# axiom_beta_plugin_module_3xmDP_v1_1.net
KiCad netlist of a schematic drawn in EAGLE
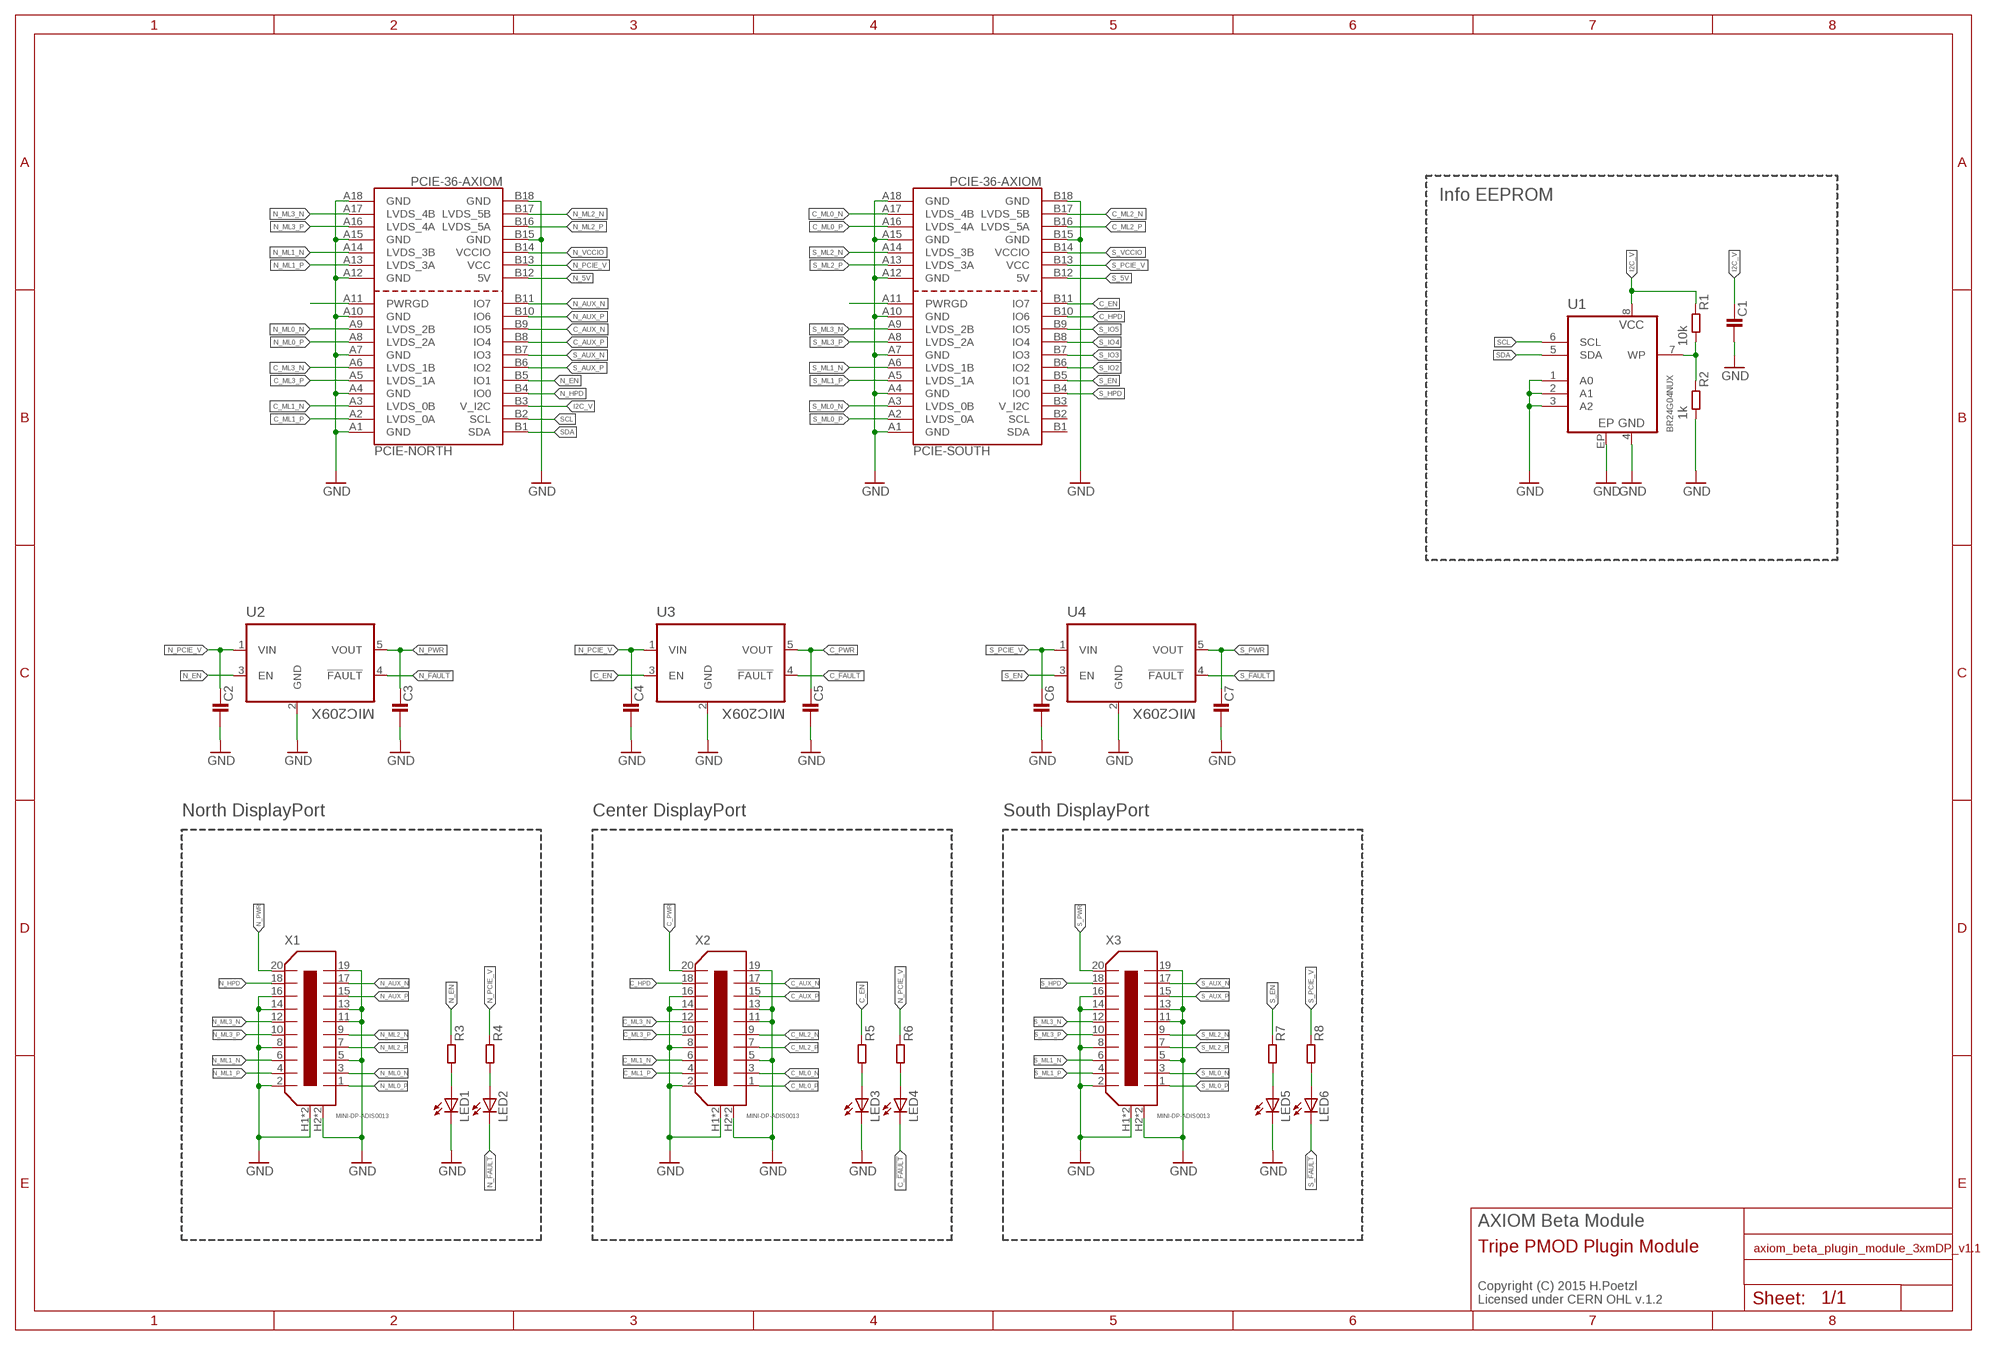
[diagram p0: schematic, sheet 1]

(export (version "E")
  (design (tool "Eeschema 10.0.6"))
  (components
    (comp (ref "C1")
      (value "C0402-B")
      (footprint "eagle-import:0402-B")
      (libsource (lib "eagle-import") (part "C0402-B"))
    )
    (comp (ref "C2")
      (value "C0603-B")
      (footprint "eagle-import:0603-B")
      (libsource (lib "eagle-import") (part "C0603-B"))
    )
    (comp (ref "C3")
      (value "C0603-B")
      (footprint "eagle-import:0603-B")
      (libsource (lib "eagle-import") (part "C0603-B"))
    )
    (comp (ref "C4")
      (value "C0603-B")
      (footprint "eagle-import:0603-B")
      (libsource (lib "eagle-import") (part "C0603-B"))
    )
    (comp (ref "C5")
      (value "C0603-B")
      (footprint "eagle-import:0603-B")
      (libsource (lib "eagle-import") (part "C0603-B"))
    )
    (comp (ref "C6")
      (value "C0603-B")
      (footprint "eagle-import:0603-B")
      (libsource (lib "eagle-import") (part "C0603-B"))
    )
    (comp (ref "C7")
      (value "C0603-B")
      (footprint "eagle-import:0603-B")
      (libsource (lib "eagle-import") (part "C0603-B"))
    )
    (comp (ref "LED1")
      (value "LEDCHIPLED_0603")
      (footprint "eagle-import:CHIPLED_0603")
      (libsource (lib "eagle-import") (part "LEDCHIPLED_0603"))
    )
    (comp (ref "LED2")
      (value "LEDCHIPLED_0603")
      (footprint "eagle-import:CHIPLED_0603")
      (libsource (lib "eagle-import") (part "LEDCHIPLED_0603"))
    )
    (comp (ref "LED3")
      (value "LEDCHIPLED_0603")
      (footprint "eagle-import:CHIPLED_0603")
      (libsource (lib "eagle-import") (part "LEDCHIPLED_0603"))
    )
    (comp (ref "LED4")
      (value "LEDCHIPLED_0603")
      (footprint "eagle-import:CHIPLED_0603")
      (libsource (lib "eagle-import") (part "LEDCHIPLED_0603"))
    )
    (comp (ref "LED5")
      (value "LEDCHIPLED_0603")
      (footprint "eagle-import:CHIPLED_0603")
      (libsource (lib "eagle-import") (part "LEDCHIPLED_0603"))
    )
    (comp (ref "LED6")
      (value "LEDCHIPLED_0603")
      (footprint "eagle-import:CHIPLED_0603")
      (libsource (lib "eagle-import") (part "LEDCHIPLED_0603"))
    )
    (comp (ref "PCIE-NORTH")
      (value "PCIE-36-AXIOM")
      (footprint "eagle-import:PCIE-36-AXIOM")
      (libsource (lib "eagle-import") (part "PCIE-36-AXIOM"))
    )
    (comp (ref "PCIE-SOUTH")
      (value "PCIE-36-AXIOM")
      (footprint "eagle-import:PCIE-36-AXIOM")
      (libsource (lib "eagle-import") (part "PCIE-36-AXIOM"))
    )
    (comp (ref "R1")
      (value "10k")
      (footprint "eagle-import:0402-B")
      (libsource (lib "eagle-import") (part "R0402-B"))
    )
    (comp (ref "R2")
      (value "1k")
      (footprint "eagle-import:0402-B")
      (libsource (lib "eagle-import") (part "R0402-B"))
    )
    (comp (ref "R3")
      (value "R0402-B")
      (footprint "eagle-import:0402-B")
      (libsource (lib "eagle-import") (part "R0402-B"))
    )
    (comp (ref "R4")
      (value "R0402-B")
      (footprint "eagle-import:0402-B")
      (libsource (lib "eagle-import") (part "R0402-B"))
    )
    (comp (ref "R5")
      (value "R0402-B")
      (footprint "eagle-import:0402-B")
      (libsource (lib "eagle-import") (part "R0402-B"))
    )
    (comp (ref "R6")
      (value "R0402-B")
      (footprint "eagle-import:0402-B")
      (libsource (lib "eagle-import") (part "R0402-B"))
    )
    (comp (ref "R7")
      (value "R0402-B")
      (footprint "eagle-import:0402-B")
      (libsource (lib "eagle-import") (part "R0402-B"))
    )
    (comp (ref "R8")
      (value "R0402-B")
      (footprint "eagle-import:0402-B")
      (libsource (lib "eagle-import") (part "R0402-B"))
    )
    (comp (ref "U1")
      (value "BR24G04NUX")
      (footprint "eagle-import:DFN200X300X100-9N")
      (libsource (lib "eagle-import") (part "BR24G04NUX"))
    )
    (comp (ref "U2")
      (value "MIC209X")
      (footprint "eagle-import:SOT95P280X145-5N")
      (fields (field (name "MPN") "MIC2090-1YM5TR"))
      (libsource (lib "eagle-import") (part "MIC209X"))
    )
    (comp (ref "U3")
      (value "MIC209X")
      (footprint "eagle-import:SOT95P280X145-5N")
      (fields (field (name "MPN") "MIC2090-1YM5TR"))
      (libsource (lib "eagle-import") (part "MIC209X"))
    )
    (comp (ref "U4")
      (value "MIC209X")
      (footprint "eagle-import:SOT95P280X145-5N")
      (fields (field (name "MPN") "MIC2090-1YM5TR"))
      (libsource (lib "eagle-import") (part "MIC209X"))
    )
    (comp (ref "X1")
      (value "MINI-DP-ADIS0013")
      (footprint "eagle-import:ADIS0013")
      (libsource (lib "eagle-import") (part "MINI-DP-ADIS0013"))
    )
    (comp (ref "X2")
      (value "MINI-DP-ADIS0013")
      (footprint "eagle-import:ADIS0013")
      (libsource (lib "eagle-import") (part "MINI-DP-ADIS0013"))
    )
    (comp (ref "X3")
      (value "MINI-DP-ADIS0013")
      (footprint "eagle-import:ADIS0013")
      (libsource (lib "eagle-import") (part "MINI-DP-ADIS0013"))
    )
  )
  (nets
    (net (code "1") (name "/C_~{FAULT}") (class "Default")
      (node (ref "LED4") (pin "C") (pinfunction "C_C") (pintype "passive"))
      (node (ref "U3") (pin "4") (pinfunction "~{FAULT}_4") (pintype "output"))
    )
    (net (code "2") (name "/N_~{FAULT}") (class "Default")
      (node (ref "LED2") (pin "C") (pinfunction "C_C") (pintype "passive"))
      (node (ref "U2") (pin "4") (pinfunction "~{FAULT}_4") (pintype "output"))
    )
    (net (code "3") (name "/S_~{FAULT}") (class "Default")
      (node (ref "LED6") (pin "C") (pinfunction "C_C") (pintype "passive"))
      (node (ref "U4") (pin "4") (pinfunction "~{FAULT}_4") (pintype "output"))
    )
    (net (code "4") (name "C_AUX_N") (class "Default")
      (node (ref "PCIE-NORTH") (pin "B9") (pinfunction "IO5_B9") (pintype "passive"))
      (node (ref "X2") (pin "17") (pinfunction "17_17") (pintype "passive"))
    )
    (net (code "5") (name "C_AUX_P") (class "Default")
      (node (ref "PCIE-NORTH") (pin "B8") (pinfunction "IO4_B8") (pintype "passive"))
      (node (ref "X2") (pin "15") (pinfunction "15_15") (pintype "passive"))
    )
    (net (code "6") (name "C_EN") (class "Default")
      (node (ref "PCIE-SOUTH") (pin "B11") (pinfunction "IO7_B11") (pintype "passive"))
      (node (ref "R5") (pin "1") (pinfunction "1_1") (pintype "passive"))
      (node (ref "U3") (pin "3") (pinfunction "EN_3") (pintype "input"))
    )
    (net (code "7") (name "C_HPD") (class "Default")
      (node (ref "PCIE-SOUTH") (pin "B10") (pinfunction "IO6_B10") (pintype "passive"))
      (node (ref "X2") (pin "18") (pinfunction "18_18") (pintype "passive"))
    )
    (net (code "8") (name "C_ML0_N") (class "Default")
      (node (ref "PCIE-SOUTH") (pin "A17") (pinfunction "LVDS_4B_A17") (pintype "passive"))
      (node (ref "X2") (pin "3") (pinfunction "3_3") (pintype "passive"))
    )
    (net (code "9") (name "C_ML0_P") (class "Default")
      (node (ref "PCIE-SOUTH") (pin "A16") (pinfunction "LVDS_4A_A16") (pintype "passive"))
      (node (ref "X2") (pin "1") (pinfunction "1_1") (pintype "passive"))
    )
    (net (code "10") (name "C_ML1_N") (class "Default")
      (node (ref "PCIE-NORTH") (pin "A3") (pinfunction "LVDS_0B_A3") (pintype "passive"))
      (node (ref "X2") (pin "6") (pinfunction "6_6") (pintype "passive"))
    )
    (net (code "11") (name "C_ML1_P") (class "Default")
      (node (ref "PCIE-NORTH") (pin "A2") (pinfunction "LVDS_0A_A2") (pintype "passive"))
      (node (ref "X2") (pin "4") (pinfunction "4_4") (pintype "passive"))
    )
    (net (code "12") (name "C_ML2_N") (class "Default")
      (node (ref "PCIE-SOUTH") (pin "B17") (pinfunction "LVDS_5B_B17") (pintype "passive"))
      (node (ref "X2") (pin "9") (pinfunction "9_9") (pintype "passive"))
    )
    (net (code "13") (name "C_ML2_P") (class "Default")
      (node (ref "PCIE-SOUTH") (pin "B16") (pinfunction "LVDS_5A_B16") (pintype "passive"))
      (node (ref "X2") (pin "7") (pinfunction "7_7") (pintype "passive"))
    )
    (net (code "14") (name "C_ML3_N") (class "Default")
      (node (ref "PCIE-NORTH") (pin "A6") (pinfunction "LVDS_1B_A6") (pintype "passive"))
      (node (ref "X2") (pin "12") (pinfunction "12_12") (pintype "passive"))
    )
    (net (code "15") (name "C_ML3_P") (class "Default")
      (node (ref "PCIE-NORTH") (pin "A5") (pinfunction "LVDS_1A_A5") (pintype "passive"))
      (node (ref "X2") (pin "10") (pinfunction "10_10") (pintype "passive"))
    )
    (net (code "16") (name "C_PWR") (class "Default")
      (node (ref "C5") (pin "1") (pinfunction "1_1") (pintype "passive"))
      (node (ref "U3") (pin "5") (pinfunction "VOUT_5") (pintype "output"))
      (node (ref "X2") (pin "20") (pinfunction "20_20") (pintype "passive"))
    )
    (net (code "17") (name "GND") (class "Default")
      (node (ref "C1") (pin "2") (pinfunction "2_2") (pintype "passive"))
      (node (ref "C2") (pin "2") (pinfunction "2_2") (pintype "passive"))
      (node (ref "C3") (pin "2") (pinfunction "2_2") (pintype "passive"))
      (node (ref "C4") (pin "2") (pinfunction "2_2") (pintype "passive"))
      (node (ref "C5") (pin "2") (pinfunction "2_2") (pintype "passive"))
      (node (ref "C6") (pin "2") (pinfunction "2_2") (pintype "passive"))
      (node (ref "C7") (pin "2") (pinfunction "2_2") (pintype "passive"))
      (node (ref "LED1") (pin "C") (pinfunction "C_C") (pintype "passive"))
      (node (ref "LED3") (pin "C") (pinfunction "C_C") (pintype "passive"))
      (node (ref "LED5") (pin "C") (pinfunction "C_C") (pintype "passive"))
      (node (ref "PCIE-NORTH") (pin "A1") (pinfunction "GND_A1") (pintype "passive"))
      (node (ref "PCIE-NORTH") (pin "A10") (pinfunction "GND_A10") (pintype "passive"))
      (node (ref "PCIE-NORTH") (pin "A12") (pinfunction "GND_A12") (pintype "passive"))
      (node (ref "PCIE-NORTH") (pin "A15") (pinfunction "GND_A15") (pintype "passive"))
      (node (ref "PCIE-NORTH") (pin "A18") (pinfunction "GND_A18") (pintype "passive"))
      (node (ref "PCIE-NORTH") (pin "A4") (pinfunction "GND_A4") (pintype "passive"))
      (node (ref "PCIE-NORTH") (pin "A7") (pinfunction "GND_A7") (pintype "passive"))
      (node (ref "PCIE-NORTH") (pin "B15") (pinfunction "GND_B15") (pintype "passive"))
      (node (ref "PCIE-NORTH") (pin "B18") (pinfunction "GND_B18") (pintype "passive"))
      (node (ref "PCIE-SOUTH") (pin "A1") (pinfunction "GND_A1") (pintype "passive"))
      (node (ref "PCIE-SOUTH") (pin "A10") (pinfunction "GND_A10") (pintype "passive"))
      (node (ref "PCIE-SOUTH") (pin "A12") (pinfunction "GND_A12") (pintype "passive"))
      (node (ref "PCIE-SOUTH") (pin "A15") (pinfunction "GND_A15") (pintype "passive"))
      (node (ref "PCIE-SOUTH") (pin "A18") (pinfunction "GND_A18") (pintype "passive"))
      (node (ref "PCIE-SOUTH") (pin "A4") (pinfunction "GND_A4") (pintype "passive"))
      (node (ref "PCIE-SOUTH") (pin "A7") (pinfunction "GND_A7") (pintype "passive"))
      (node (ref "PCIE-SOUTH") (pin "B15") (pinfunction "GND_B15") (pintype "passive"))
      (node (ref "PCIE-SOUTH") (pin "B18") (pinfunction "GND_B18") (pintype "passive"))
      (node (ref "R2") (pin "2") (pinfunction "2_2") (pintype "passive"))
      (node (ref "U1") (pin "1") (pinfunction "A0_1") (pintype "input"))
      (node (ref "U1") (pin "2") (pinfunction "A1_2") (pintype "input"))
      (node (ref "U1") (pin "3") (pinfunction "A2_3") (pintype "input"))
      (node (ref "U1") (pin "4") (pinfunction "GND_4") (pintype "passive"))
      (node (ref "U1") (pin "EP") (pinfunction "EP_EP") (pintype "passive"))
      (node (ref "U2") (pin "2") (pinfunction "GND_2") (pintype "passive"))
      (node (ref "U3") (pin "2") (pinfunction "GND_2") (pintype "passive"))
      (node (ref "U4") (pin "2") (pinfunction "GND_2") (pintype "passive"))
      (node (ref "X1") (pin "11") (pinfunction "11_11") (pintype "passive"))
      (node (ref "X1") (pin "13") (pinfunction "13_13") (pintype "passive"))
      (node (ref "X1") (pin "14") (pinfunction "14_14") (pintype "passive"))
      (node (ref "X1") (pin "16") (pinfunction "16_16") (pintype "passive"))
      (node (ref "X1") (pin "19") (pinfunction "19_19") (pintype "passive"))
      (node (ref "X1") (pin "2") (pinfunction "2_2") (pintype "passive"))
      (node (ref "X1") (pin "5") (pinfunction "5_5") (pintype "passive"))
      (node (ref "X1") (pin "8") (pinfunction "8_8") (pintype "passive"))
      (node (ref "X1") (pin "H1") (pinfunction "M_H1") (pintype "input"))
      (node (ref "X1") (pin "H2") (pinfunction "M_H2") (pintype "input"))
      (node (ref "X1") (pin "H3") (pinfunction "M_H3") (pintype "input"))
      (node (ref "X1") (pin "H4") (pinfunction "M_H4") (pintype "input"))
      (node (ref "X2") (pin "11") (pinfunction "11_11") (pintype "passive"))
      (node (ref "X2") (pin "13") (pinfunction "13_13") (pintype "passive"))
      (node (ref "X2") (pin "14") (pinfunction "14_14") (pintype "passive"))
      (node (ref "X2") (pin "16") (pinfunction "16_16") (pintype "passive"))
      (node (ref "X2") (pin "19") (pinfunction "19_19") (pintype "passive"))
      (node (ref "X2") (pin "2") (pinfunction "2_2") (pintype "passive"))
      (node (ref "X2") (pin "5") (pinfunction "5_5") (pintype "passive"))
      (node (ref "X2") (pin "8") (pinfunction "8_8") (pintype "passive"))
      (node (ref "X2") (pin "H1") (pinfunction "M_H1") (pintype "input"))
      (node (ref "X2") (pin "H2") (pinfunction "M_H2") (pintype "input"))
      (node (ref "X2") (pin "H3") (pinfunction "M_H3") (pintype "input"))
      (node (ref "X2") (pin "H4") (pinfunction "M_H4") (pintype "input"))
      (node (ref "X3") (pin "11") (pinfunction "11_11") (pintype "passive"))
      (node (ref "X3") (pin "13") (pinfunction "13_13") (pintype "passive"))
      (node (ref "X3") (pin "14") (pinfunction "14_14") (pintype "passive"))
      (node (ref "X3") (pin "16") (pinfunction "16_16") (pintype "passive"))
      (node (ref "X3") (pin "19") (pinfunction "19_19") (pintype "passive"))
      (node (ref "X3") (pin "2") (pinfunction "2_2") (pintype "passive"))
      (node (ref "X3") (pin "5") (pinfunction "5_5") (pintype "passive"))
      (node (ref "X3") (pin "8") (pinfunction "8_8") (pintype "passive"))
      (node (ref "X3") (pin "H1") (pinfunction "M_H1") (pintype "input"))
      (node (ref "X3") (pin "H2") (pinfunction "M_H2") (pintype "input"))
      (node (ref "X3") (pin "H3") (pinfunction "M_H3") (pintype "input"))
      (node (ref "X3") (pin "H4") (pinfunction "M_H4") (pintype "input"))
    )
    (net (code "18") (name "I2C_V") (class "Default")
      (node (ref "C1") (pin "1") (pinfunction "1_1") (pintype "passive"))
      (node (ref "PCIE-NORTH") (pin "B3") (pinfunction "V_I2C_B3") (pintype "passive"))
      (node (ref "R1") (pin "1") (pinfunction "1_1") (pintype "passive"))
      (node (ref "U1") (pin "8") (pinfunction "VCC_8") (pintype "power_in"))
    )
    (net (code "19") (name "N_5V") (class "Default")
      (node (ref "PCIE-NORTH") (pin "B12") (pinfunction "5V_B12") (pintype "passive"))
    )
    (net (code "20") (name "N_AUX_N") (class "Default")
      (node (ref "PCIE-NORTH") (pin "B11") (pinfunction "IO7_B11") (pintype "passive"))
      (node (ref "X1") (pin "17") (pinfunction "17_17") (pintype "passive"))
    )
    (net (code "21") (name "N_AUX_P") (class "Default")
      (node (ref "PCIE-NORTH") (pin "B10") (pinfunction "IO6_B10") (pintype "passive"))
      (node (ref "X1") (pin "15") (pinfunction "15_15") (pintype "passive"))
    )
    (net (code "22") (name "N_EN") (class "Default")
      (node (ref "PCIE-NORTH") (pin "B5") (pinfunction "IO1_B5") (pintype "passive"))
      (node (ref "R3") (pin "1") (pinfunction "1_1") (pintype "passive"))
      (node (ref "U2") (pin "3") (pinfunction "EN_3") (pintype "input"))
    )
    (net (code "23") (name "N_HPD") (class "Default")
      (node (ref "PCIE-NORTH") (pin "B4") (pinfunction "IO0_B4") (pintype "passive"))
      (node (ref "X1") (pin "18") (pinfunction "18_18") (pintype "passive"))
    )
    (net (code "24") (name "N_ML0_N") (class "Default")
      (node (ref "PCIE-NORTH") (pin "A9") (pinfunction "LVDS_2B_A9") (pintype "passive"))
      (node (ref "X1") (pin "3") (pinfunction "3_3") (pintype "passive"))
    )
    (net (code "25") (name "N_ML0_P") (class "Default")
      (node (ref "PCIE-NORTH") (pin "A8") (pinfunction "LVDS_2A_A8") (pintype "passive"))
      (node (ref "X1") (pin "1") (pinfunction "1_1") (pintype "passive"))
    )
    (net (code "26") (name "N_ML1_N") (class "Default")
      (node (ref "PCIE-NORTH") (pin "A14") (pinfunction "LVDS_3B_A14") (pintype "passive"))
      (node (ref "X1") (pin "6") (pinfunction "6_6") (pintype "passive"))
    )
    (net (code "27") (name "N_ML1_P") (class "Default")
      (node (ref "PCIE-NORTH") (pin "A13") (pinfunction "LVDS_3A_A13") (pintype "passive"))
      (node (ref "X1") (pin "4") (pinfunction "4_4") (pintype "passive"))
    )
    (net (code "28") (name "N_ML2_N") (class "Default")
      (node (ref "PCIE-NORTH") (pin "B17") (pinfunction "LVDS_5B_B17") (pintype "passive"))
      (node (ref "X1") (pin "9") (pinfunction "9_9") (pintype "passive"))
    )
    (net (code "29") (name "N_ML2_P") (class "Default")
      (node (ref "PCIE-NORTH") (pin "B16") (pinfunction "LVDS_5A_B16") (pintype "passive"))
      (node (ref "X1") (pin "7") (pinfunction "7_7") (pintype "passive"))
    )
    (net (code "30") (name "N_ML3_N") (class "Default")
      (node (ref "PCIE-NORTH") (pin "A17") (pinfunction "LVDS_4B_A17") (pintype "passive"))
      (node (ref "X1") (pin "12") (pinfunction "12_12") (pintype "passive"))
    )
    (net (code "31") (name "N_ML3_P") (class "Default")
      (node (ref "PCIE-NORTH") (pin "A16") (pinfunction "LVDS_4A_A16") (pintype "passive"))
      (node (ref "X1") (pin "10") (pinfunction "10_10") (pintype "passive"))
    )
    (net (code "32") (name "N_PCIE_V") (class "Default")
      (node (ref "C2") (pin "1") (pinfunction "1_1") (pintype "passive"))
      (node (ref "C4") (pin "1") (pinfunction "1_1") (pintype "passive"))
      (node (ref "PCIE-NORTH") (pin "B13") (pinfunction "VCC_B13") (pintype "passive"))
      (node (ref "R4") (pin "1") (pinfunction "1_1") (pintype "passive"))
      (node (ref "R6") (pin "1") (pinfunction "1_1") (pintype "passive"))
      (node (ref "U2") (pin "1") (pinfunction "VIN_1") (pintype "input"))
      (node (ref "U3") (pin "1") (pinfunction "VIN_1") (pintype "input"))
    )
    (net (code "33") (name "N_PWR") (class "Default")
      (node (ref "C3") (pin "1") (pinfunction "1_1") (pintype "passive"))
      (node (ref "U2") (pin "5") (pinfunction "VOUT_5") (pintype "output"))
      (node (ref "X1") (pin "20") (pinfunction "20_20") (pintype "passive"))
    )
    (net (code "34") (name "N_VCCIO") (class "Default")
      (node (ref "PCIE-NORTH") (pin "B14") (pinfunction "VCCIO_B14") (pintype "passive"))
    )
    (net (code "35") (name "Net-(LED1-PadA)") (class "Default")
      (node (ref "LED1") (pin "A") (pinfunction "A_A") (pintype "passive"))
      (node (ref "R3") (pin "2") (pinfunction "2_2") (pintype "passive"))
    )
    (net (code "36") (name "Net-(LED2-PadA)") (class "Default")
      (node (ref "LED2") (pin "A") (pinfunction "A_A") (pintype "passive"))
      (node (ref "R4") (pin "2") (pinfunction "2_2") (pintype "passive"))
    )
    (net (code "37") (name "Net-(LED3-PadA)") (class "Default")
      (node (ref "LED3") (pin "A") (pinfunction "A_A") (pintype "passive"))
      (node (ref "R5") (pin "2") (pinfunction "2_2") (pintype "passive"))
    )
    (net (code "38") (name "Net-(LED4-PadA)") (class "Default")
      (node (ref "LED4") (pin "A") (pinfunction "A_A") (pintype "passive"))
      (node (ref "R6") (pin "2") (pinfunction "2_2") (pintype "passive"))
    )
    (net (code "39") (name "Net-(LED5-PadA)") (class "Default")
      (node (ref "LED5") (pin "A") (pinfunction "A_A") (pintype "passive"))
      (node (ref "R7") (pin "2") (pinfunction "2_2") (pintype "passive"))
    )
    (net (code "40") (name "Net-(LED6-PadA)") (class "Default")
      (node (ref "LED6") (pin "A") (pinfunction "A_A") (pintype "passive"))
      (node (ref "R8") (pin "2") (pinfunction "2_2") (pintype "passive"))
    )
    (net (code "41") (name "Net-(U1-WP)") (class "Default")
      (node (ref "R1") (pin "2") (pinfunction "2_2") (pintype "passive"))
      (node (ref "R2") (pin "1") (pinfunction "1_1") (pintype "passive"))
      (node (ref "U1") (pin "7") (pinfunction "WP_7") (pintype "input"))
    )
    (net (code "42") (name "SCL") (class "Default")
      (node (ref "PCIE-NORTH") (pin "B2") (pinfunction "SCL_B2") (pintype "passive"))
      (node (ref "U1") (pin "6") (pinfunction "SCL_6") (pintype "input"))
    )
    (net (code "43") (name "SDA") (class "Default")
      (node (ref "PCIE-NORTH") (pin "B1") (pinfunction "SDA_B1") (pintype "passive"))
      (node (ref "U1") (pin "5") (pinfunction "SDA_5") (pintype "bidirectional"))
    )
    (net (code "44") (name "S_5V") (class "Default")
      (node (ref "PCIE-SOUTH") (pin "B12") (pinfunction "5V_B12") (pintype "passive"))
    )
    (net (code "45") (name "S_AUX_N") (class "Default")
      (node (ref "PCIE-NORTH") (pin "B7") (pinfunction "IO3_B7") (pintype "passive"))
      (node (ref "X3") (pin "17") (pinfunction "17_17") (pintype "passive"))
    )
    (net (code "46") (name "S_AUX_P") (class "Default")
      (node (ref "PCIE-NORTH") (pin "B6") (pinfunction "IO2_B6") (pintype "passive"))
      (node (ref "X3") (pin "15") (pinfunction "15_15") (pintype "passive"))
    )
    (net (code "47") (name "S_EN") (class "Default")
      (node (ref "PCIE-SOUTH") (pin "B5") (pinfunction "IO1_B5") (pintype "passive"))
      (node (ref "R7") (pin "1") (pinfunction "1_1") (pintype "passive"))
      (node (ref "U4") (pin "3") (pinfunction "EN_3") (pintype "input"))
    )
    (net (code "48") (name "S_HPD") (class "Default")
      (node (ref "PCIE-SOUTH") (pin "B4") (pinfunction "IO0_B4") (pintype "passive"))
      (node (ref "X3") (pin "18") (pinfunction "18_18") (pintype "passive"))
    )
    (net (code "49") (name "S_IO2") (class "Default")
      (node (ref "PCIE-SOUTH") (pin "B6") (pinfunction "IO2_B6") (pintype "passive"))
    )
    (net (code "50") (name "S_IO3") (class "Default")
      (node (ref "PCIE-SOUTH") (pin "B7") (pinfunction "IO3_B7") (pintype "passive"))
    )
    (net (code "51") (name "S_IO4") (class "Default")
      (node (ref "PCIE-SOUTH") (pin "B8") (pinfunction "IO4_B8") (pintype "passive"))
    )
    (net (code "52") (name "S_IO5") (class "Default")
      (node (ref "PCIE-SOUTH") (pin "B9") (pinfunction "IO5_B9") (pintype "passive"))
    )
    (net (code "53") (name "S_ML0_N") (class "Default")
      (node (ref "PCIE-SOUTH") (pin "A3") (pinfunction "LVDS_0B_A3") (pintype "passive"))
      (node (ref "X3") (pin "3") (pinfunction "3_3") (pintype "passive"))
    )
    (net (code "54") (name "S_ML0_P") (class "Default")
      (node (ref "PCIE-SOUTH") (pin "A2") (pinfunction "LVDS_0A_A2") (pintype "passive"))
      (node (ref "X3") (pin "1") (pinfunction "1_1") (pintype "passive"))
    )
    (net (code "55") (name "S_ML1_N") (class "Default")
      (node (ref "PCIE-SOUTH") (pin "A6") (pinfunction "LVDS_1B_A6") (pintype "passive"))
      (node (ref "X3") (pin "6") (pinfunction "6_6") (pintype "passive"))
    )
    (net (code "56") (name "S_ML1_P") (class "Default")
      (node (ref "PCIE-SOUTH") (pin "A5") (pinfunction "LVDS_1A_A5") (pintype "passive"))
      (node (ref "X3") (pin "4") (pinfunction "4_4") (pintype "passive"))
    )
    (net (code "57") (name "S_ML2_N") (class "Default")
      (node (ref "PCIE-SOUTH") (pin "A14") (pinfunction "LVDS_3B_A14") (pintype "passive"))
      (node (ref "X3") (pin "9") (pinfunction "9_9") (pintype "passive"))
    )
    (net (code "58") (name "S_ML2_P") (class "Default")
      (node (ref "PCIE-SOUTH") (pin "A13") (pinfunction "LVDS_3A_A13") (pintype "passive"))
      (node (ref "X3") (pin "7") (pinfunction "7_7") (pintype "passive"))
    )
    (net (code "59") (name "S_ML3_N") (class "Default")
      (node (ref "PCIE-SOUTH") (pin "A9") (pinfunction "LVDS_2B_A9") (pintype "passive"))
      (node (ref "X3") (pin "12") (pinfunction "12_12") (pintype "passive"))
    )
    (net (code "60") (name "S_ML3_P") (class "Default")
      (node (ref "PCIE-SOUTH") (pin "A8") (pinfunction "LVDS_2A_A8") (pintype "passive"))
      (node (ref "X3") (pin "10") (pinfunction "10_10") (pintype "passive"))
    )
    (net (code "61") (name "S_PCIE_V") (class "Default")
      (node (ref "C6") (pin "1") (pinfunction "1_1") (pintype "passive"))
      (node (ref "PCIE-SOUTH") (pin "B13") (pinfunction "VCC_B13") (pintype "passive"))
      (node (ref "R8") (pin "1") (pinfunction "1_1") (pintype "passive"))
      (node (ref "U4") (pin "1") (pinfunction "VIN_1") (pintype "input"))
    )
    (net (code "62") (name "S_PWR") (class "Default")
      (node (ref "C7") (pin "1") (pinfunction "1_1") (pintype "passive"))
      (node (ref "U4") (pin "5") (pinfunction "VOUT_5") (pintype "output"))
      (node (ref "X3") (pin "20") (pinfunction "20_20") (pintype "passive"))
    )
    (net (code "63") (name "S_VCCIO") (class "Default")
      (node (ref "PCIE-SOUTH") (pin "B14") (pinfunction "VCCIO_B14") (pintype "passive"))
    )
    (net (code "64") (name "unconnected-(PCIE-NORTH-PWRGD-PadA11)") (class "Default")
      (node (ref "PCIE-NORTH") (pin "A11") (pinfunction "PWRGD_A11") (pintype "passive"))
    )
    (net (code "65") (name "unconnected-(PCIE-SOUTH-PWRGD-PadA11)") (class "Default")
      (node (ref "PCIE-SOUTH") (pin "A11") (pinfunction "PWRGD_A11") (pintype "passive"))
    )
    (net (code "66") (name "unconnected-(PCIE-SOUTH-SCL-PadB2)") (class "Default")
      (node (ref "PCIE-SOUTH") (pin "B2") (pinfunction "SCL_B2") (pintype "passive"))
    )
    (net (code "67") (name "unconnected-(PCIE-SOUTH-SDA-PadB1)") (class "Default")
      (node (ref "PCIE-SOUTH") (pin "B1") (pinfunction "SDA_B1") (pintype "passive"))
    )
    (net (code "68") (name "unconnected-(PCIE-SOUTH-V_I2C-PadB3)") (class "Default")
      (node (ref "PCIE-SOUTH") (pin "B3") (pinfunction "V_I2C_B3") (pintype "passive"))
    )
  )
)
